# teensy_amp_loads_of_switches.net
KiCad netlist of a schematic drawn in EAGLE
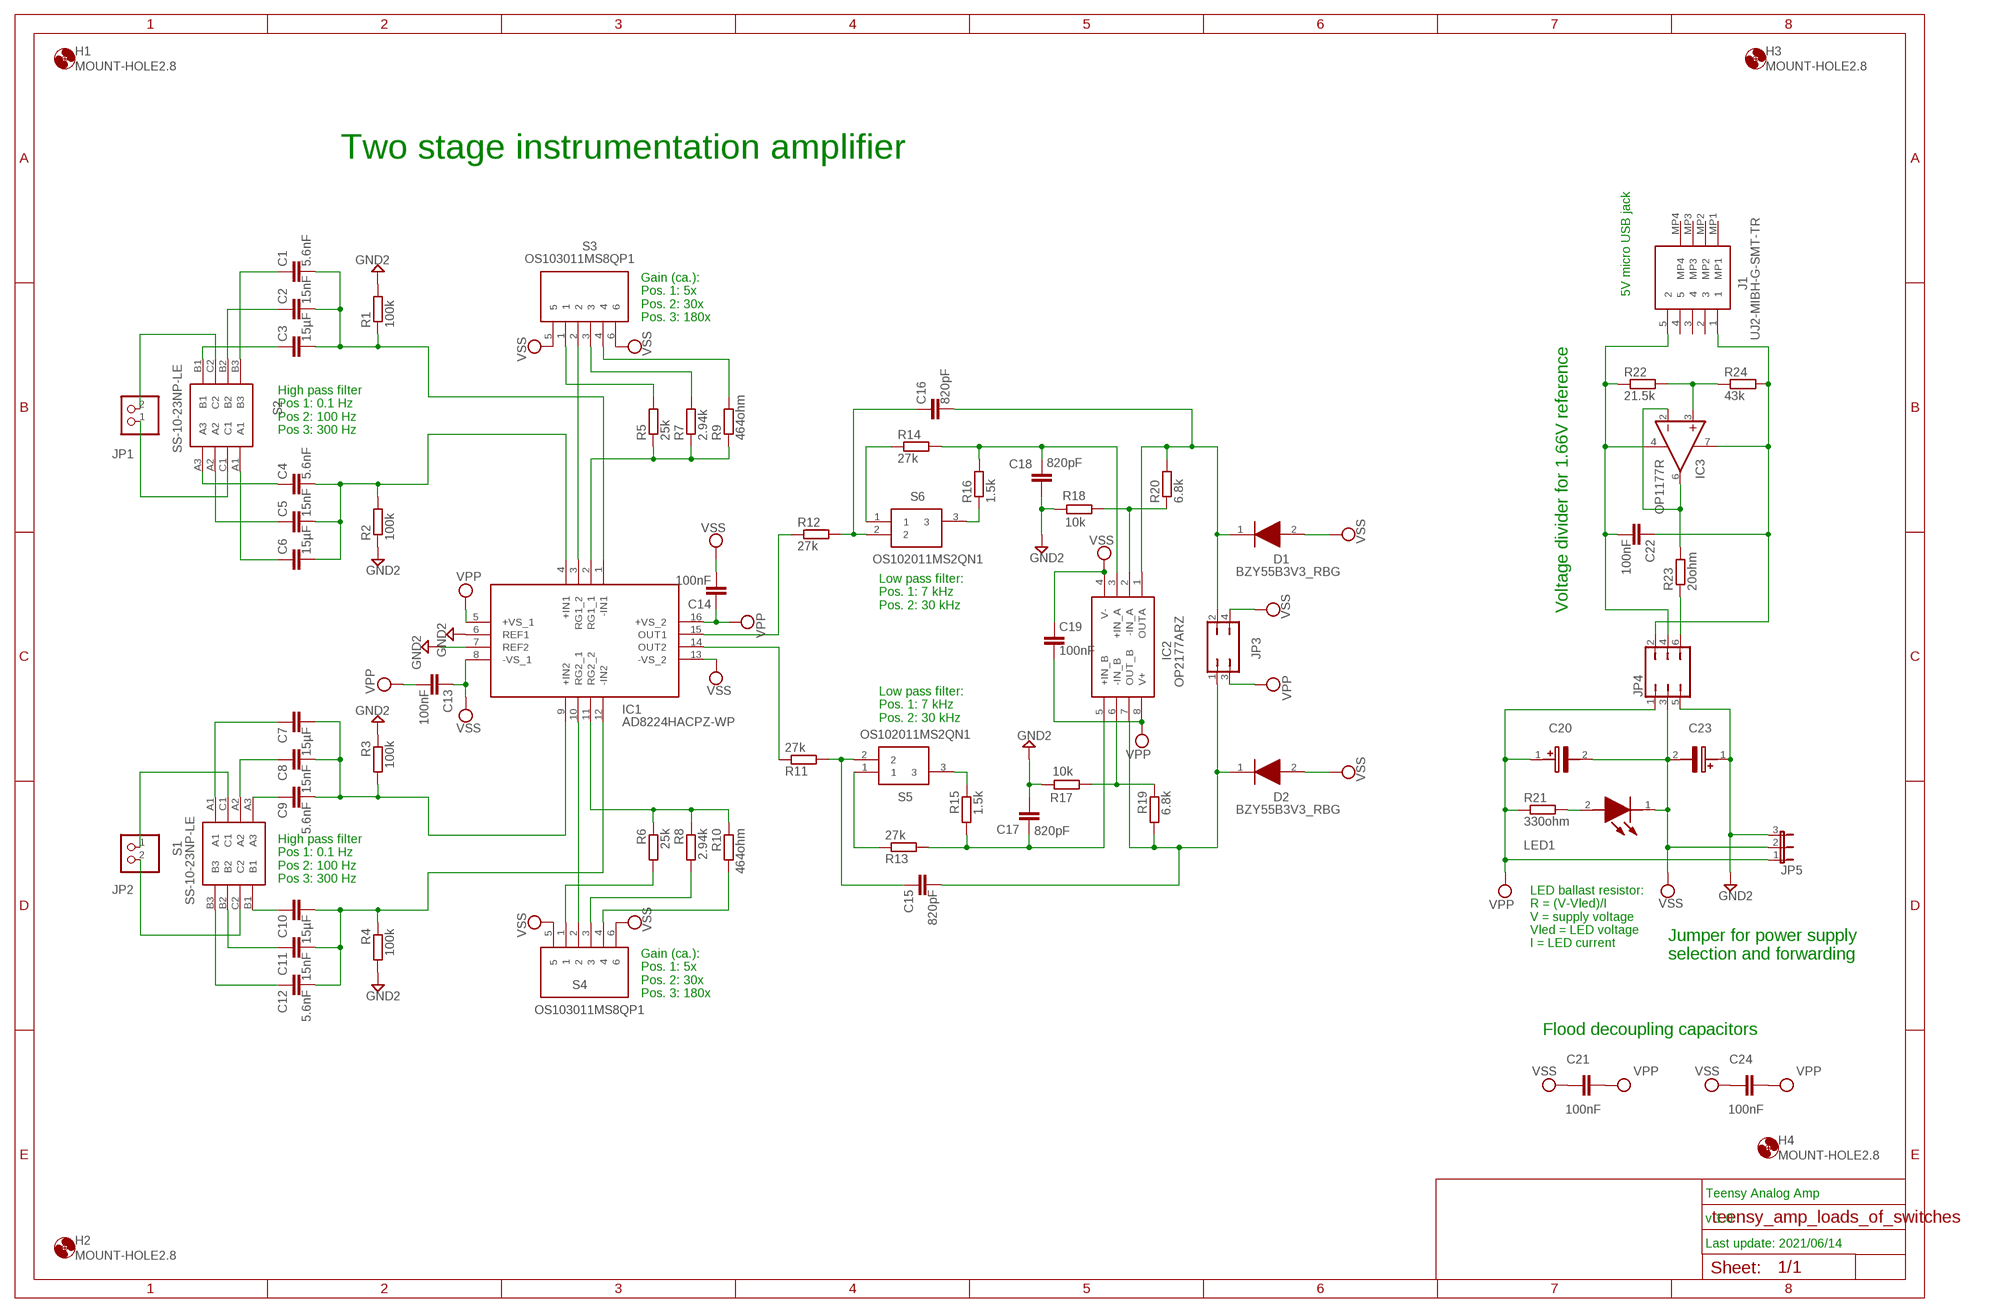
[diagram p0: schematic, sheet 1]

(export (version "E")
  (design (tool "Eeschema 10.0.6"))
  (components
    (comp (ref "C1")
      (value "5.6nF")
      (footprint "eagle-import:C0805")
      (libsource (lib "eagle-import") (part "C-EUC0805"))
    )
    (comp (ref "C2")
      (value "15nF")
      (footprint "eagle-import:C0805")
      (libsource (lib "eagle-import") (part "C-EUC0805"))
    )
    (comp (ref "C3")
      (value "15µF")
      (footprint "eagle-import:C0805")
      (libsource (lib "eagle-import") (part "C-EUC0805"))
    )
    (comp (ref "C4")
      (value "5.6nF")
      (footprint "eagle-import:C0805")
      (libsource (lib "eagle-import") (part "C-EUC0805"))
    )
    (comp (ref "C5")
      (value "15nF")
      (footprint "eagle-import:C0805")
      (libsource (lib "eagle-import") (part "C-EUC0805"))
    )
    (comp (ref "C6")
      (value "15µF")
      (footprint "eagle-import:C0805")
      (libsource (lib "eagle-import") (part "C-EUC0805"))
    )
    (comp (ref "C7")
      (value "15µF")
      (footprint "eagle-import:C0805")
      (libsource (lib "eagle-import") (part "C-EUC0805"))
    )
    (comp (ref "C8")
      (value "15nF")
      (footprint "eagle-import:C0805")
      (libsource (lib "eagle-import") (part "C-EUC0805"))
    )
    (comp (ref "C9")
      (value "5.6nF")
      (footprint "eagle-import:C0805")
      (libsource (lib "eagle-import") (part "C-EUC0805"))
    )
    (comp (ref "C10")
      (value "15µF")
      (footprint "eagle-import:C0805")
      (libsource (lib "eagle-import") (part "C-EUC0805"))
    )
    (comp (ref "C11")
      (value "15nF")
      (footprint "eagle-import:C0805")
      (libsource (lib "eagle-import") (part "C-EUC0805"))
    )
    (comp (ref "C12")
      (value "5.6nF")
      (footprint "eagle-import:C0805")
      (libsource (lib "eagle-import") (part "C-EUC0805"))
    )
    (comp (ref "C13")
      (value "100nF")
      (footprint "eagle-import:C0805")
      (libsource (lib "eagle-import") (part "C-EUC0805"))
    )
    (comp (ref "C14")
      (value "100nF")
      (footprint "eagle-import:C0805")
      (libsource (lib "eagle-import") (part "C-EUC0805"))
    )
    (comp (ref "C15")
      (value "820pF")
      (footprint "eagle-import:C0805")
      (libsource (lib "eagle-import") (part "C-EUC0805"))
    )
    (comp (ref "C16")
      (value "820pF")
      (footprint "eagle-import:C0805")
      (libsource (lib "eagle-import") (part "C-EUC0805"))
    )
    (comp (ref "C17")
      (value "820pF")
      (footprint "eagle-import:C0805")
      (libsource (lib "eagle-import") (part "C-EUC0805"))
    )
    (comp (ref "C18")
      (value "820pF")
      (footprint "eagle-import:C0805")
      (libsource (lib "eagle-import") (part "C-EUC0805"))
    )
    (comp (ref "C19")
      (value "100nF")
      (footprint "eagle-import:C0805")
      (libsource (lib "eagle-import") (part "C-EUC0805"))
    )
    (comp (ref "C20")
      (value "TAJA475K010RNJV")
      (footprint "eagle-import:CAPPM3216X180N")
      (fields (field (name "MOUSER_PART_NUMBER") "581-TAJA475K010RNJV"))
      (libsource (lib "eagle-import") (part "TAJA475K010RNJV"))
    )
    (comp (ref "C21")
      (value "100nF")
      (footprint "eagle-import:C0805")
      (libsource (lib "eagle-import") (part "C-EUC0805"))
    )
    (comp (ref "C22")
      (value "100nF")
      (footprint "eagle-import:C0805")
      (libsource (lib "eagle-import") (part "C-EUC0805"))
    )
    (comp (ref "C23")
      (value "TAJA475K010RNJV")
      (footprint "eagle-import:CAPPM3216X180N")
      (fields (field (name "MOUSER_PART_NUMBER") "581-TAJA475K010RNJV"))
      (libsource (lib "eagle-import") (part "TAJA475K010RNJV"))
    )
    (comp (ref "C24")
      (value "100nF")
      (footprint "eagle-import:C0805")
      (libsource (lib "eagle-import") (part "C-EUC0805"))
    )
    (comp (ref "D1")
      (value "BZY55B3V3_RBG")
      (footprint "eagle-import:BZY55B3V3RBG")
      (fields
        (field (name "MANUFACTURER_PART_NUMBER") "BZY55B3V3 RBG")
        (field (name "MOUSER_PART_NUMBER") "821-BZY55B3V3RBG")
      )
      (libsource (lib "eagle-import") (part "BZY55B3V3_RBG"))
    )
    (comp (ref "D2")
      (value "BZY55B3V3_RBG")
      (footprint "eagle-import:BZY55B3V3RBG")
      (fields
        (field (name "MANUFACTURER_PART_NUMBER") "BZY55B3V3 RBG")
        (field (name "MOUSER_PART_NUMBER") "821-BZY55B3V3RBG")
      )
      (libsource (lib "eagle-import") (part "BZY55B3V3_RBG"))
    )
    (comp (ref "H1")
      (value "MOUNT-HOLE2.8")
      (footprint "eagle-import:2,8")
      (libsource (lib "eagle-import") (part "MOUNT-HOLE2.8"))
    )
    (comp (ref "H2")
      (value "MOUNT-HOLE2.8")
      (footprint "eagle-import:2,8")
      (libsource (lib "eagle-import") (part "MOUNT-HOLE2.8"))
    )
    (comp (ref "H3")
      (value "MOUNT-HOLE2.8")
      (footprint "eagle-import:2,8")
      (libsource (lib "eagle-import") (part "MOUNT-HOLE2.8"))
    )
    (comp (ref "H4")
      (value "MOUNT-HOLE2.8")
      (footprint "eagle-import:2,8")
      (libsource (lib "eagle-import") (part "MOUNT-HOLE2.8"))
    )
    (comp (ref "IC1")
      (value "AD8224HACPZ-WP")
      (footprint "eagle-import:QFN65P400X400X100-16N")
      (fields (field (name "MOUSER_PART_NUMBER") "584-AD8224HACPZ-WP"))
      (libsource (lib "eagle-import") (part "AD8224HACPZ-WP"))
    )
    (comp (ref "IC2")
      (value "OP2177ARZ")
      (footprint "eagle-import:SOIC127P600X175-8N")
      (fields (field (name "MOUSER_PART_NUMBER") "584-OP2177ARZ"))
      (libsource (lib "eagle-import") (part "OP2177ARZ"))
    )
    (comp (ref "IC3")
      (value "OP1177R")
      (footprint "eagle-import:SOIC8")
      (libsource (lib "eagle-import") (part "OP1177R"))
    )
    (comp (ref "J1")
      (value "UJ2-MIBH-G-SMT-TR")
      (footprint "eagle-import:UJ2MIBHGSMTTR")
      (fields (field (name "MOUSER_PART_NUMBER") "490-UJ2-MIBH-G-SMTTR"))
      (libsource (lib "eagle-import") (part "UJ2-MIBH-G-SMT-TR"))
    )
    (comp (ref "JP1")
      (value "PINHD-1X2")
      (footprint "eagle-import:1X02")
      (libsource (lib "eagle-import") (part "PINHD-1X2"))
    )
    (comp (ref "JP2")
      (value "PINHD-1X2")
      (footprint "eagle-import:1X02")
      (libsource (lib "eagle-import") (part "PINHD-1X2"))
    )
    (comp (ref "JP3")
      (value "JP2Q")
      (footprint "eagle-import:JP2Q")
      (libsource (lib "eagle-import") (part "JP2Q"))
    )
    (comp (ref "JP4")
      (value "JP3Q")
      (footprint "eagle-import:JP3Q")
      (libsource (lib "eagle-import") (part "JP3Q"))
    )
    (comp (ref "JP5")
      (value "JP2E")
      (footprint "eagle-import:JP2")
      (libsource (lib "eagle-import") (part "JP2E"))
    )
    (comp (ref "LED1")
      (value "150060RS75000")
      (footprint "eagle-import:LEDC1608X80N")
      (fields (field (name "MOUSER_PART_NUMBER") "710-150060RS75000"))
      (libsource (lib "eagle-import") (part "150060RS75000"))
    )
    (comp (ref "R1")
      (value "100k")
      (footprint "eagle-import:R0805")
      (libsource (lib "eagle-import") (part "R-EU_R0805"))
    )
    (comp (ref "R2")
      (value "100k")
      (footprint "eagle-import:R0805")
      (libsource (lib "eagle-import") (part "R-EU_R0805"))
    )
    (comp (ref "R3")
      (value "100k")
      (footprint "eagle-import:R0805")
      (libsource (lib "eagle-import") (part "R-EU_R0805"))
    )
    (comp (ref "R4")
      (value "100k")
      (footprint "eagle-import:R0805")
      (libsource (lib "eagle-import") (part "R-EU_R0805"))
    )
    (comp (ref "R5")
      (value "25k")
      (footprint "eagle-import:R0805")
      (libsource (lib "eagle-import") (part "R-EU_R0805"))
    )
    (comp (ref "R6")
      (value "25k")
      (footprint "eagle-import:R0805")
      (libsource (lib "eagle-import") (part "R-EU_R0805"))
    )
    (comp (ref "R7")
      (value "2.94k")
      (footprint "eagle-import:R0805")
      (libsource (lib "eagle-import") (part "R-EU_R0805"))
    )
    (comp (ref "R8")
      (value "2.94k")
      (footprint "eagle-import:R0805")
      (libsource (lib "eagle-import") (part "R-EU_R0805"))
    )
    (comp (ref "R9")
      (value "464ohm")
      (footprint "eagle-import:R0805")
      (libsource (lib "eagle-import") (part "R-EU_R0805"))
    )
    (comp (ref "R10")
      (value "464ohm")
      (footprint "eagle-import:R0805")
      (libsource (lib "eagle-import") (part "R-EU_R0805"))
    )
    (comp (ref "R11")
      (value "27k")
      (footprint "eagle-import:R0805")
      (libsource (lib "eagle-import") (part "R-EU_R0805"))
    )
    (comp (ref "R12")
      (value "27k")
      (footprint "eagle-import:R0805")
      (libsource (lib "eagle-import") (part "R-EU_R0805"))
    )
    (comp (ref "R13")
      (value "27k")
      (footprint "eagle-import:R0805")
      (libsource (lib "eagle-import") (part "R-EU_R0805"))
    )
    (comp (ref "R14")
      (value "27k")
      (footprint "eagle-import:R0805")
      (libsource (lib "eagle-import") (part "R-EU_R0805"))
    )
    (comp (ref "R15")
      (value "1.5k")
      (footprint "eagle-import:R0805")
      (libsource (lib "eagle-import") (part "R-EU_R0805"))
    )
    (comp (ref "R16")
      (value "1.5k")
      (footprint "eagle-import:R0805")
      (libsource (lib "eagle-import") (part "R-EU_R0805"))
    )
    (comp (ref "R17")
      (value "10k")
      (footprint "eagle-import:R0805")
      (libsource (lib "eagle-import") (part "R-EU_R0805"))
    )
    (comp (ref "R18")
      (value "10k")
      (footprint "eagle-import:R0805")
      (libsource (lib "eagle-import") (part "R-EU_R0805"))
    )
    (comp (ref "R19")
      (value "6.8k")
      (footprint "eagle-import:R0805")
      (libsource (lib "eagle-import") (part "R-EU_R0805"))
    )
    (comp (ref "R20")
      (value "6.8k")
      (footprint "eagle-import:R0805")
      (libsource (lib "eagle-import") (part "R-EU_R0805"))
    )
    (comp (ref "R21")
      (value "330ohm")
      (footprint "eagle-import:R0805")
      (libsource (lib "eagle-import") (part "R-EU_R0805"))
    )
    (comp (ref "R22")
      (value "21.5k")
      (footprint "eagle-import:R0805")
      (libsource (lib "eagle-import") (part "R-EU_R0805"))
    )
    (comp (ref "R23")
      (value "20ohm")
      (footprint "eagle-import:R0805")
      (libsource (lib "eagle-import") (part "R-EU_R0805"))
    )
    (comp (ref "R24")
      (value "43k")
      (footprint "eagle-import:R0805")
      (libsource (lib "eagle-import") (part "R-EU_R0805"))
    )
    (comp (ref "S1")
      (value "SS-10-23NP-LE")
      (footprint "eagle-import:SS1023NPLE")
      (libsource (lib "eagle-import") (part "SS-10-23NP-LE"))
    )
    (comp (ref "S2")
      (value "SS-10-23NP-LE")
      (footprint "eagle-import:SS1023NPLE")
      (libsource (lib "eagle-import") (part "SS-10-23NP-LE"))
    )
    (comp (ref "S3")
      (value "OS103011MS8QP1")
      (footprint "eagle-import:OS103011MS8QP1")
      (fields (field (name "MOUSER_PART_NUMBER") "611-OS103011MS8QP1"))
      (libsource (lib "eagle-import") (part "OS103011MS8QP1"))
    )
    (comp (ref "S4")
      (value "OS103011MS8QP1")
      (footprint "eagle-import:OS103011MS8QP1")
      (fields (field (name "MOUSER_PART_NUMBER") "611-OS103011MS8QP1"))
      (libsource (lib "eagle-import") (part "OS103011MS8QP1"))
    )
    (comp (ref "S5")
      (value "OS102011MS2QN1")
      (footprint "eagle-import:OS102011MA1QN1")
      (fields (field (name "MOUSER_PART_NUMBER") "611-OS102011MS2QN1"))
      (libsource (lib "eagle-import") (part "OS102011MS2QN1"))
    )
    (comp (ref "S6")
      (value "OS102011MS2QN1")
      (footprint "eagle-import:OS102011MA1QN1")
      (fields (field (name "MOUSER_PART_NUMBER") "611-OS102011MS2QN1"))
      (libsource (lib "eagle-import") (part "OS102011MS2QN1"))
    )
  )
  (nets
    (net (code "1") (name "GND2") (class "Default")
      (node (ref "C17") (pin "2") (pinfunction "2_2") (pintype "passive"))
      (node (ref "C18") (pin "2") (pinfunction "2_2") (pintype "passive"))
      (node (ref "C23") (pin "1") (pinfunction "+_1") (pintype "bidirectional"))
      (node (ref "IC1") (pin "6") (pinfunction "REF1_6") (pintype "bidirectional"))
      (node (ref "IC1") (pin "7") (pinfunction "REF2_7") (pintype "bidirectional"))
      (node (ref "JP4") (pin "5") (pinfunction "5_5") (pintype "passive"))
      (node (ref "JP5") (pin "3") (pinfunction "3_3") (pintype "passive"))
      (node (ref "R1") (pin "2") (pinfunction "2_2") (pintype "passive"))
      (node (ref "R17") (pin "2") (pinfunction "2_2") (pintype "passive"))
      (node (ref "R18") (pin "2") (pinfunction "2_2") (pintype "passive"))
      (node (ref "R2") (pin "1") (pinfunction "1_1") (pintype "passive"))
      (node (ref "R3") (pin "1") (pinfunction "1_1") (pintype "passive"))
      (node (ref "R4") (pin "2") (pinfunction "2_2") (pintype "passive"))
    )
    (net (code "2") (name "Net-(C1-Pad1)") (class "Default")
      (node (ref "C1") (pin "1") (pinfunction "1_1") (pintype "passive"))
      (node (ref "S2") (pin "B3") (pinfunction "B3_B3") (pintype "bidirectional"))
    )
    (net (code "3") (name "Net-(C2-Pad1)") (class "Default")
      (node (ref "C2") (pin "1") (pinfunction "1_1") (pintype "passive"))
      (node (ref "S2") (pin "B2") (pinfunction "B2_B2") (pintype "bidirectional"))
    )
    (net (code "4") (name "Net-(C3-Pad1)") (class "Default")
      (node (ref "C3") (pin "1") (pinfunction "1_1") (pintype "passive"))
      (node (ref "S2") (pin "B1") (pinfunction "B1_B1") (pintype "bidirectional"))
    )
    (net (code "5") (name "Net-(C4-Pad1)") (class "Default")
      (node (ref "C4") (pin "1") (pinfunction "1_1") (pintype "passive"))
      (node (ref "S2") (pin "A3") (pinfunction "A3_A3") (pintype "bidirectional"))
    )
    (net (code "6") (name "Net-(C5-Pad1)") (class "Default")
      (node (ref "C5") (pin "1") (pinfunction "1_1") (pintype "passive"))
      (node (ref "S2") (pin "A2") (pinfunction "A2_A2") (pintype "bidirectional"))
    )
    (net (code "7") (name "Net-(C6-Pad1)") (class "Default")
      (node (ref "C6") (pin "1") (pinfunction "1_1") (pintype "passive"))
      (node (ref "S2") (pin "A1") (pinfunction "A1_A1") (pintype "bidirectional"))
    )
    (net (code "8") (name "Net-(C7-Pad1)") (class "Default")
      (node (ref "C7") (pin "1") (pinfunction "1_1") (pintype "passive"))
      (node (ref "S1") (pin "A1") (pinfunction "A1_A1") (pintype "bidirectional"))
    )
    (net (code "9") (name "Net-(C8-Pad1)") (class "Default")
      (node (ref "C8") (pin "1") (pinfunction "1_1") (pintype "passive"))
      (node (ref "S1") (pin "A2") (pinfunction "A2_A2") (pintype "bidirectional"))
    )
    (net (code "10") (name "Net-(C9-Pad1)") (class "Default")
      (node (ref "C9") (pin "1") (pinfunction "1_1") (pintype "passive"))
      (node (ref "S1") (pin "A3") (pinfunction "A3_A3") (pintype "bidirectional"))
    )
    (net (code "11") (name "Net-(C10-Pad1)") (class "Default")
      (node (ref "C10") (pin "1") (pinfunction "1_1") (pintype "passive"))
      (node (ref "S1") (pin "B1") (pinfunction "B1_B1") (pintype "bidirectional"))
    )
    (net (code "12") (name "Net-(C11-Pad1)") (class "Default")
      (node (ref "C11") (pin "1") (pinfunction "1_1") (pintype "passive"))
      (node (ref "S1") (pin "B2") (pinfunction "B2_B2") (pintype "bidirectional"))
    )
    (net (code "13") (name "Net-(C12-Pad1)") (class "Default")
      (node (ref "C12") (pin "1") (pinfunction "1_1") (pintype "passive"))
      (node (ref "S1") (pin "B3") (pinfunction "B3_B3") (pintype "bidirectional"))
    )
    (net (code "14") (name "Net-(C15-Pad1)") (class "Default")
      (node (ref "C15") (pin "1") (pinfunction "1_1") (pintype "passive"))
      (node (ref "R11") (pin "2") (pinfunction "2_2") (pintype "passive"))
      (node (ref "S5") (pin "2") (pinfunction "2_2") (pintype "bidirectional"))
    )
    (net (code "15") (name "Net-(C16-Pad1)") (class "Default")
      (node (ref "C16") (pin "1") (pinfunction "1_1") (pintype "passive"))
      (node (ref "R12") (pin "2") (pinfunction "2_2") (pintype "passive"))
      (node (ref "S6") (pin "2") (pinfunction "2_2") (pintype "bidirectional"))
    )
    (net (code "16") (name "Net-(D1-K)") (class "Default")
      (node (ref "C16") (pin "2") (pinfunction "2_2") (pintype "passive"))
      (node (ref "D1") (pin "1") (pinfunction "K_1") (pintype "bidirectional"))
      (node (ref "IC2") (pin "1") (pinfunction "OUTA_1") (pintype "bidirectional"))
      (node (ref "JP3") (pin "2") (pinfunction "2_2") (pintype "passive"))
      (node (ref "R20") (pin "2") (pinfunction "2_2") (pintype "passive"))
    )
    (net (code "17") (name "Net-(D2-K)") (class "Default")
      (node (ref "C15") (pin "2") (pinfunction "2_2") (pintype "passive"))
      (node (ref "D2") (pin "1") (pinfunction "K_1") (pintype "bidirectional"))
      (node (ref "IC2") (pin "7") (pinfunction "OUT_B_7") (pintype "bidirectional"))
      (node (ref "JP3") (pin "1") (pinfunction "1_1") (pintype "passive"))
      (node (ref "R19") (pin "2") (pinfunction "2_2") (pintype "passive"))
    )
    (net (code "18") (name "Net-(IC1-+IN1)") (class "Default")
      (node (ref "C4") (pin "2") (pinfunction "2_2") (pintype "passive"))
      (node (ref "C5") (pin "2") (pinfunction "2_2") (pintype "passive"))
      (node (ref "C6") (pin "2") (pinfunction "2_2") (pintype "passive"))
      (node (ref "IC1") (pin "4") (pinfunction "+IN1_4") (pintype "bidirectional"))
      (node (ref "R2") (pin "2") (pinfunction "2_2") (pintype "passive"))
    )
    (net (code "19") (name "Net-(IC1-+IN2)") (class "Default")
      (node (ref "C7") (pin "2") (pinfunction "2_2") (pintype "passive"))
      (node (ref "C8") (pin "2") (pinfunction "2_2") (pintype "passive"))
      (node (ref "C9") (pin "2") (pinfunction "2_2") (pintype "passive"))
      (node (ref "IC1") (pin "9") (pinfunction "+IN2_9") (pintype "bidirectional"))
      (node (ref "R3") (pin "2") (pinfunction "2_2") (pintype "passive"))
    )
    (net (code "20") (name "Net-(IC1--IN1)") (class "Default")
      (node (ref "C1") (pin "2") (pinfunction "2_2") (pintype "passive"))
      (node (ref "C2") (pin "2") (pinfunction "2_2") (pintype "passive"))
      (node (ref "C3") (pin "2") (pinfunction "2_2") (pintype "passive"))
      (node (ref "IC1") (pin "1") (pinfunction "-IN1_1") (pintype "bidirectional"))
      (node (ref "R1") (pin "1") (pinfunction "1_1") (pintype "passive"))
    )
    (net (code "21") (name "Net-(IC1--IN2)") (class "Default")
      (node (ref "C10") (pin "2") (pinfunction "2_2") (pintype "passive"))
      (node (ref "C11") (pin "2") (pinfunction "2_2") (pintype "passive"))
      (node (ref "C12") (pin "2") (pinfunction "2_2") (pintype "passive"))
      (node (ref "IC1") (pin "12") (pinfunction "-IN2_12") (pintype "bidirectional"))
      (node (ref "R4") (pin "1") (pinfunction "1_1") (pintype "passive"))
    )
    (net (code "22") (name "Net-(IC1-OUT1)") (class "Default")
      (node (ref "IC1") (pin "15") (pinfunction "OUT1_15") (pintype "bidirectional"))
      (node (ref "R12") (pin "1") (pinfunction "1_1") (pintype "passive"))
    )
    (net (code "23") (name "Net-(IC1-OUT2)") (class "Default")
      (node (ref "IC1") (pin "14") (pinfunction "OUT2_14") (pintype "bidirectional"))
      (node (ref "R11") (pin "1") (pinfunction "1_1") (pintype "passive"))
    )
    (net (code "24") (name "Net-(IC1-RG1_1)") (class "Default")
      (node (ref "IC1") (pin "2") (pinfunction "RG1_1_2") (pintype "bidirectional"))
      (node (ref "R5") (pin "1") (pinfunction "1_1") (pintype "passive"))
      (node (ref "R7") (pin "1") (pinfunction "1_1") (pintype "passive"))
      (node (ref "R9") (pin "1") (pinfunction "1_1") (pintype "passive"))
    )
    (net (code "25") (name "Net-(IC1-RG1_2)") (class "Default")
      (node (ref "IC1") (pin "3") (pinfunction "RG1_2_3") (pintype "bidirectional"))
      (node (ref "S3") (pin "2") (pinfunction "2_2") (pintype "bidirectional"))
    )
    (net (code "26") (name "Net-(IC1-RG2_1)") (class "Default")
      (node (ref "IC1") (pin "10") (pinfunction "RG2_1_10") (pintype "bidirectional"))
      (node (ref "S4") (pin "2") (pinfunction "2_2") (pintype "bidirectional"))
    )
    (net (code "27") (name "Net-(IC1-RG2_2)") (class "Default")
      (node (ref "IC1") (pin "11") (pinfunction "RG2_2_11") (pintype "bidirectional"))
      (node (ref "R10") (pin "1") (pinfunction "1_1") (pintype "passive"))
      (node (ref "R6") (pin "1") (pinfunction "1_1") (pintype "passive"))
      (node (ref "R8") (pin "1") (pinfunction "1_1") (pintype "passive"))
    )
    (net (code "28") (name "Net-(IC2-+IN_A)") (class "Default")
      (node (ref "C18") (pin "1") (pinfunction "1_1") (pintype "passive"))
      (node (ref "IC2") (pin "3") (pinfunction "+IN_A_3") (pintype "bidirectional"))
      (node (ref "R14") (pin "2") (pinfunction "2_2") (pintype "passive"))
      (node (ref "R16") (pin "2") (pinfunction "2_2") (pintype "passive"))
    )
    (net (code "29") (name "Net-(IC2-+IN_B)") (class "Default")
      (node (ref "C17") (pin "1") (pinfunction "1_1") (pintype "passive"))
      (node (ref "IC2") (pin "5") (pinfunction "+IN_B_5") (pintype "bidirectional"))
      (node (ref "R13") (pin "2") (pinfunction "2_2") (pintype "passive"))
      (node (ref "R15") (pin "2") (pinfunction "2_2") (pintype "passive"))
    )
    (net (code "30") (name "Net-(IC2--IN_A)") (class "Default")
      (node (ref "IC2") (pin "2") (pinfunction "-IN_A_2") (pintype "bidirectional"))
      (node (ref "R18") (pin "1") (pinfunction "1_1") (pintype "passive"))
      (node (ref "R20") (pin "1") (pinfunction "1_1") (pintype "passive"))
    )
    (net (code "31") (name "Net-(IC2--IN_B)") (class "Default")
      (node (ref "IC2") (pin "6") (pinfunction "-IN_B_6") (pintype "bidirectional"))
      (node (ref "R17") (pin "1") (pinfunction "1_1") (pintype "passive"))
      (node (ref "R19") (pin "1") (pinfunction "1_1") (pintype "passive"))
    )
    (net (code "32") (name "Net-(IC3-+IN)") (class "Default")
      (node (ref "IC3") (pin "3") (pinfunction "+IN_3") (pintype "input"))
      (node (ref "R22") (pin "2") (pinfunction "2_2") (pintype "passive"))
      (node (ref "R24") (pin "1") (pinfunction "1_1") (pintype "passive"))
    )
    (net (code "33") (name "Net-(IC3--IN)") (class "Default")
      (node (ref "IC3") (pin "2") (pinfunction "-IN_2") (pintype "input"))
      (node (ref "IC3") (pin "6") (pinfunction "OUT_6") (pintype "output"))
      (node (ref "R23") (pin "2") (pinfunction "2_2") (pintype "passive"))
    )
    (net (code "34") (name "Net-(IC3-V+)") (class "Default")
      (node (ref "C22") (pin "1") (pinfunction "1_1") (pintype "passive"))
      (node (ref "IC3") (pin "7") (pinfunction "V+_7") (pintype "power_in"))
      (node (ref "J1") (pin "1") (pinfunction "1_1") (pintype "bidirectional"))
      (node (ref "JP4") (pin "2") (pinfunction "2_2") (pintype "passive"))
      (node (ref "R24") (pin "2") (pinfunction "2_2") (pintype "passive"))
    )
    (net (code "35") (name "Net-(IC3-V-)") (class "Default")
      (node (ref "C22") (pin "2") (pinfunction "2_2") (pintype "passive"))
      (node (ref "IC3") (pin "4") (pinfunction "V-_4") (pintype "power_in"))
      (node (ref "J1") (pin "5") (pinfunction "2_5") (pintype "bidirectional"))
      (node (ref "JP4") (pin "4") (pinfunction "4_4") (pintype "passive"))
      (node (ref "R22") (pin "1") (pinfunction "1_1") (pintype "passive"))
    )
    (net (code "36") (name "Net-(JP1-Pad1)") (class "Default")
      (node (ref "JP1") (pin "1") (pinfunction "1_1") (pintype "passive"))
      (node (ref "S2") (pin "C1") (pinfunction "C1_C1") (pintype "bidirectional"))
    )
    (net (code "37") (name "Net-(JP1-Pad2)") (class "Default")
      (node (ref "JP1") (pin "2") (pinfunction "2_2") (pintype "passive"))
      (node (ref "S2") (pin "C2") (pinfunction "C2_C2") (pintype "bidirectional"))
    )
    (net (code "38") (name "Net-(JP2-Pad1)") (class "Default")
      (node (ref "JP2") (pin "1") (pinfunction "1_1") (pintype "passive"))
      (node (ref "S1") (pin "C1") (pinfunction "C1_C1") (pintype "bidirectional"))
    )
    (net (code "39") (name "Net-(JP2-Pad2)") (class "Default")
      (node (ref "JP2") (pin "2") (pinfunction "2_2") (pintype "passive"))
      (node (ref "S1") (pin "C2") (pinfunction "C2_C2") (pintype "bidirectional"))
    )
    (net (code "40") (name "Net-(JP4-Pad6)") (class "Default")
      (node (ref "JP4") (pin "6") (pinfunction "6_6") (pintype "passive"))
      (node (ref "R23") (pin "1") (pinfunction "1_1") (pintype "passive"))
    )
    (net (code "41") (name "Net-(LED1-A)") (class "Default")
      (node (ref "LED1") (pin "2") (pinfunction "A_2") (pintype "bidirectional"))
      (node (ref "R21") (pin "2") (pinfunction "2_2") (pintype "passive"))
    )
    (net (code "42") (name "Net-(R5-Pad2)") (class "Default")
      (node (ref "R5") (pin "2") (pinfunction "2_2") (pintype "passive"))
      (node (ref "S3") (pin "1") (pinfunction "1_1") (pintype "bidirectional"))
    )
    (net (code "43") (name "Net-(R6-Pad2)") (class "Default")
      (node (ref "R6") (pin "2") (pinfunction "2_2") (pintype "passive"))
      (node (ref "S4") (pin "1") (pinfunction "1_1") (pintype "bidirectional"))
    )
    (net (code "44") (name "Net-(R7-Pad2)") (class "Default")
      (node (ref "R7") (pin "2") (pinfunction "2_2") (pintype "passive"))
      (node (ref "S3") (pin "3") (pinfunction "3_3") (pintype "bidirectional"))
    )
    (net (code "45") (name "Net-(R8-Pad2)") (class "Default")
      (node (ref "R8") (pin "2") (pinfunction "2_2") (pintype "passive"))
      (node (ref "S4") (pin "3") (pinfunction "3_3") (pintype "bidirectional"))
    )
    (net (code "46") (name "Net-(R9-Pad2)") (class "Default")
      (node (ref "R9") (pin "2") (pinfunction "2_2") (pintype "passive"))
      (node (ref "S3") (pin "4") (pinfunction "4_4") (pintype "bidirectional"))
    )
    (net (code "47") (name "Net-(R10-Pad2)") (class "Default")
      (node (ref "R10") (pin "2") (pinfunction "2_2") (pintype "passive"))
      (node (ref "S4") (pin "4") (pinfunction "4_4") (pintype "bidirectional"))
    )
    (net (code "48") (name "Net-(R13-Pad1)") (class "Default")
      (node (ref "R13") (pin "1") (pinfunction "1_1") (pintype "passive"))
      (node (ref "S5") (pin "1") (pinfunction "1_1") (pintype "bidirectional"))
    )
    (net (code "49") (name "Net-(R14-Pad1)") (class "Default")
      (node (ref "R14") (pin "1") (pinfunction "1_1") (pintype "passive"))
      (node (ref "S6") (pin "1") (pinfunction "1_1") (pintype "bidirectional"))
    )
    (net (code "50") (name "Net-(R15-Pad1)") (class "Default")
      (node (ref "R15") (pin "1") (pinfunction "1_1") (pintype "passive"))
      (node (ref "S5") (pin "3") (pinfunction "3_3") (pintype "bidirectional"))
    )
    (net (code "51") (name "Net-(R16-Pad1)") (class "Default")
      (node (ref "R16") (pin "1") (pinfunction "1_1") (pintype "passive"))
      (node (ref "S6") (pin "3") (pinfunction "3_3") (pintype "bidirectional"))
    )
    (net (code "52") (name "VPP") (class "Default")
      (node (ref "C13") (pin "2") (pinfunction "2_2") (pintype "passive"))
      (node (ref "C14") (pin "1") (pinfunction "1_1") (pintype "passive"))
      (node (ref "C19") (pin "2") (pinfunction "2_2") (pintype "passive"))
      (node (ref "C20") (pin "1") (pinfunction "+_1") (pintype "bidirectional"))
      (node (ref "C21") (pin "2") (pinfunction "2_2") (pintype "passive"))
      (node (ref "C24") (pin "2") (pinfunction "2_2") (pintype "passive"))
      (node (ref "IC1") (pin "16") (pinfunction "+VS_2_16") (pintype "bidirectional"))
      (node (ref "IC1") (pin "5") (pinfunction "+VS_1_5") (pintype "bidirectional"))
      (node (ref "IC2") (pin "8") (pinfunction "V+_8") (pintype "bidirectional"))
      (node (ref "JP3") (pin "3") (pinfunction "3_3") (pintype "passive"))
      (node (ref "JP4") (pin "1") (pinfunction "1_1") (pintype "passive"))
      (node (ref "JP5") (pin "1") (pinfunction "1_1") (pintype "passive"))
      (node (ref "R21") (pin "1") (pinfunction "1_1") (pintype "passive"))
    )
    (net (code "53") (name "VSS") (class "Default")
      (node (ref "C13") (pin "1") (pinfunction "1_1") (pintype "passive"))
      (node (ref "C14") (pin "2") (pinfunction "2_2") (pintype "passive"))
      (node (ref "C19") (pin "1") (pinfunction "1_1") (pintype "passive"))
      (node (ref "C20") (pin "2") (pinfunction "-_2") (pintype "bidirectional"))
      (node (ref "C21") (pin "1") (pinfunction "1_1") (pintype "passive"))
      (node (ref "C23") (pin "2") (pinfunction "-_2") (pintype "bidirectional"))
      (node (ref "C24") (pin "1") (pinfunction "1_1") (pintype "passive"))
      (node (ref "D1") (pin "2") (pinfunction "A_2") (pintype "bidirectional"))
      (node (ref "D2") (pin "2") (pinfunction "A_2") (pintype "bidirectional"))
      (node (ref "IC1") (pin "13") (pinfunction "-VS_2_13") (pintype "bidirectional"))
      (node (ref "IC1") (pin "8") (pinfunction "-VS_1_8") (pintype "bidirectional"))
      (node (ref "IC2") (pin "4") (pinfunction "V-_4") (pintype "bidirectional"))
      (node (ref "JP3") (pin "4") (pinfunction "4_4") (pintype "passive"))
      (node (ref "JP4") (pin "3") (pinfunction "3_3") (pintype "passive"))
      (node (ref "JP5") (pin "2") (pinfunction "2_2") (pintype "passive"))
      (node (ref "LED1") (pin "1") (pinfunction "K_1") (pintype "bidirectional"))
      (node (ref "S3") (pin "5") (pinfunction "5_5") (pintype "bidirectional"))
      (node (ref "S3") (pin "6") (pinfunction "6_6") (pintype "bidirectional"))
      (node (ref "S4") (pin "5") (pinfunction "5_5") (pintype "bidirectional"))
      (node (ref "S4") (pin "6") (pinfunction "6_6") (pintype "bidirectional"))
    )
    (net (code "54") (name "unconnected-(J1-3-Pad2)") (class "Default")
      (node (ref "J1") (pin "2") (pinfunction "3_2") (pintype "bidirectional"))
    )
    (net (code "55") (name "unconnected-(J1-4-Pad3)") (class "Default")
      (node (ref "J1") (pin "3") (pinfunction "4_3") (pintype "bidirectional"))
    )
    (net (code "56") (name "unconnected-(J1-5-Pad4)") (class "Default")
      (node (ref "J1") (pin "4") (pinfunction "5_4") (pintype "bidirectional"))
    )
    (net (code "57") (name "unconnected-(J1-PadMP1)") (class "Default")
      (node (ref "J1") (pin "MP1") (pinfunction "MP1_MP1") (pintype "bidirectional"))
    )
    (net (code "58") (name "unconnected-(J1-PadMP2)") (class "Default")
      (node (ref "J1") (pin "MP2") (pinfunction "MP2_MP2") (pintype "bidirectional"))
    )
    (net (code "59") (name "unconnected-(J1-PadMP3)") (class "Default")
      (node (ref "J1") (pin "MP3") (pinfunction "MP3_MP3") (pintype "bidirectional"))
    )
    (net (code "60") (name "unconnected-(J1-PadMP4)") (class "Default")
      (node (ref "J1") (pin "MP4") (pinfunction "MP4_MP4") (pintype "bidirectional"))
    )
  )
)
